# ospi_v12.net
KiCad netlist of a schematic drawn in EAGLE
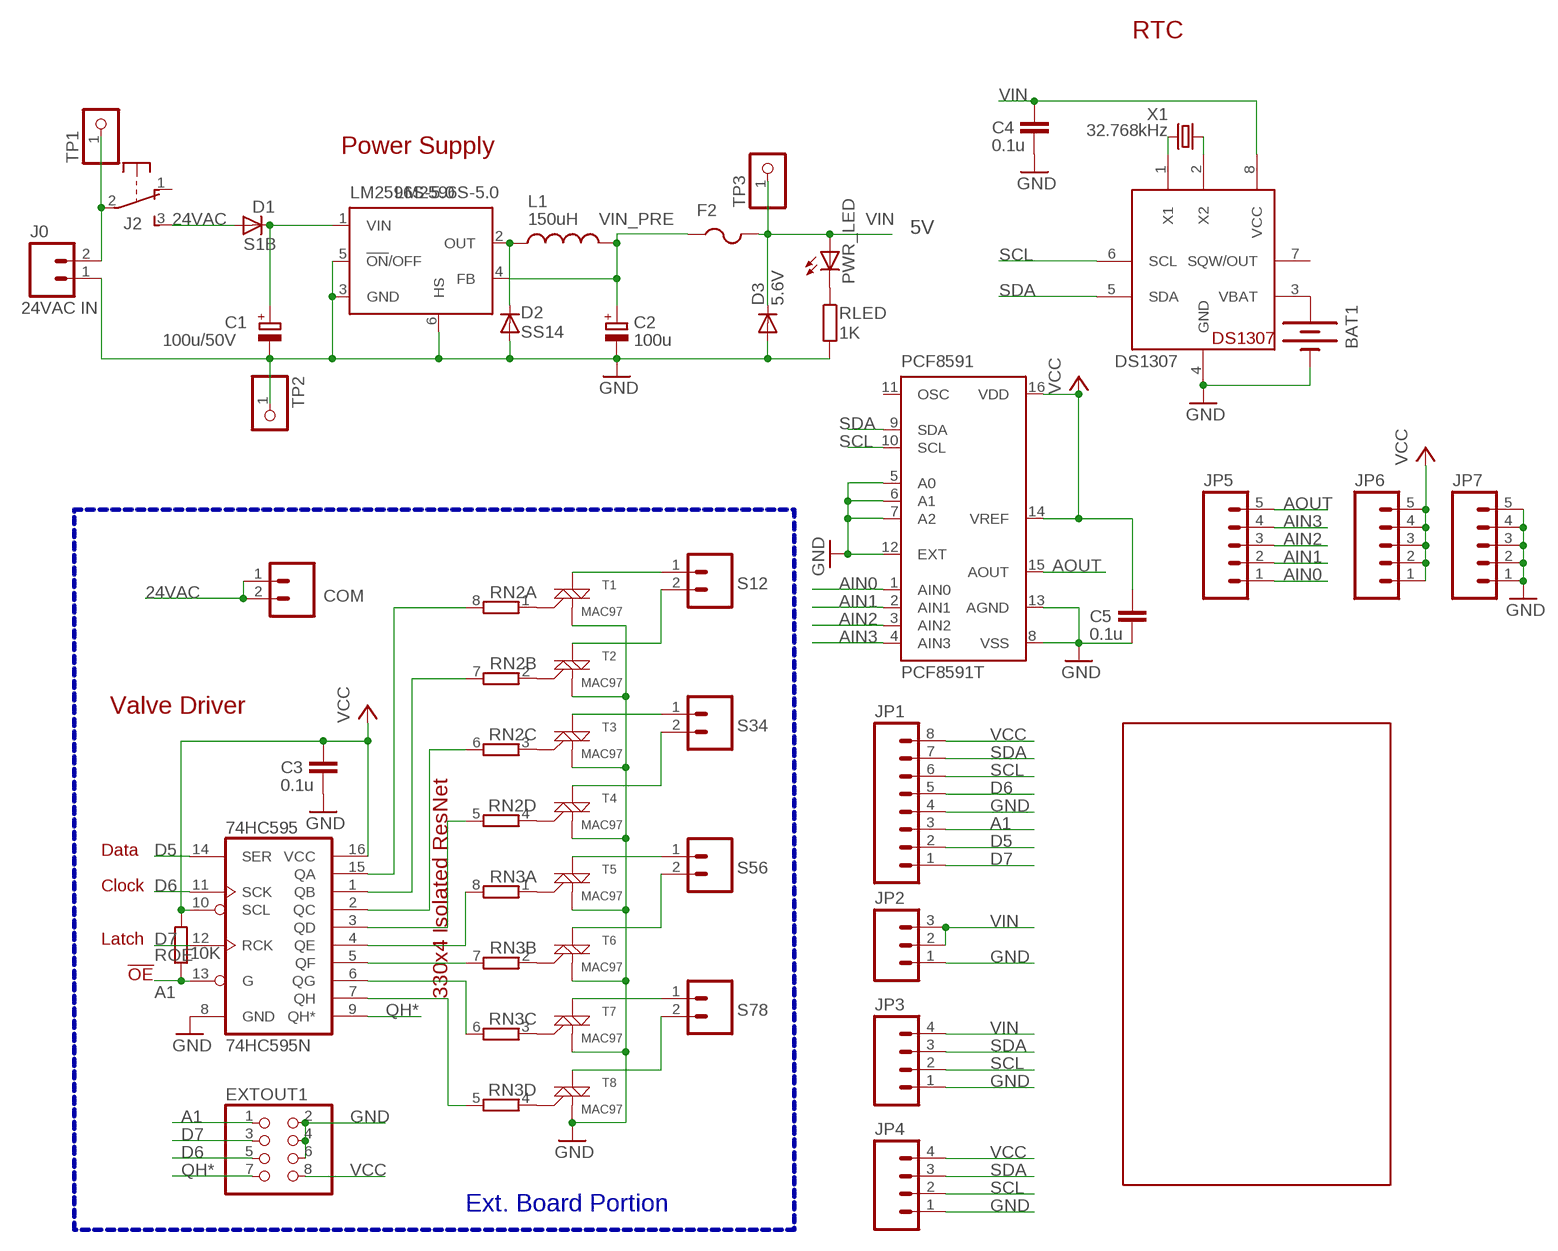
[diagram p0: schematic, sheet 1]

(export (version "E")
  (design (tool "Eeschema 10.0.6"))
  (components
    (comp (ref "74HC595")
      (value "74HC595N")
      (footprint "eagle-import:SO16")
      (libsource (lib "eagle-import") (part "74595DLS"))
    )
    (comp (ref "BAT1")
      (value "BATTERYBATTERY_12MM_SMT")
      (footprint "eagle-import:BATTCON_12MM_SMT")
      (libsource (lib "eagle-import") (part "BATTERYBATTERY_12MM_SMT"))
    )
    (comp (ref "C1")
      (value "100u/50V")
      (footprint "eagle-import:PANASONIC_E")
      (libsource (lib "eagle-import") (part "CPOL-EUE"))
    )
    (comp (ref "C2")
      (value "100u")
      (footprint "eagle-import:PANASONIC_E")
      (libsource (lib "eagle-import") (part "CPOL-EUE"))
    )
    (comp (ref "C3")
      (value "0.1u")
      (footprint "eagle-import:C0805")
      (libsource (lib "eagle-import") (part "C-EUC0805"))
    )
    (comp (ref "C4")
      (value "0.1u")
      (footprint "eagle-import:C0805")
      (libsource (lib "eagle-import") (part "C-EUC0805"))
    )
    (comp (ref "C5")
      (value "0.1u")
      (footprint "eagle-import:C0805")
      (libsource (lib "eagle-import") (part "C-EUC0805"))
    )
    (comp (ref "COM")
      (value "M025MM")
      (footprint "eagle-import:SCREWTERMINAL-5MM-2")
      (libsource (lib "eagle-import") (part "M025MM"))
    )
    (comp (ref "D1")
      (value "S1B")
      (footprint "eagle-import:DO-214AC")
      (libsource (lib "eagle-import") (part "DIODE-DO-214AC"))
    )
    (comp (ref "D2")
      (value "SS14")
      (footprint "eagle-import:DO-214AC")
      (libsource (lib "eagle-import") (part "DIODE-DO-214AC"))
    )
    (comp (ref "D3")
      (value "5.6V")
      (footprint "eagle-import:MINIMELF")
      (libsource (lib "eagle-import") (part "DIODE-MINIMELF"))
    )
    (comp (ref "DS1307")
      (value "DS1307")
      (footprint "eagle-import:SO08")
      (libsource (lib "eagle-import") (part "DS1307SOIC"))
    )
    (comp (ref "EXTOUT1")
      (value "PINHD-2X4/90")
      (footprint "eagle-import:2X04_90")
      (libsource (lib "eagle-import") (part "PINHD-2X4/90"))
    )
    (comp (ref "F2")
      (value "PTCFUSE-1812")
      (footprint "eagle-import:1812")
      (libsource (lib "eagle-import") (part "PTCFUSE-1812"))
    )
    (comp (ref "J0")
      (value "24VAC IN")
      (footprint "eagle-import:SCREWTERMINAL-5MM-2")
      (libsource (lib "eagle-import") (part "M025MM"))
    )
    (comp (ref "J2")
      (value "EG1206")
      (footprint "eagle-import:EG1206")
      (libsource (lib "eagle-import") (part "EG1206"))
    )
    (comp (ref "JP1")
      (value "M08LOCK")
      (footprint "eagle-import:1X08_LOCK")
      (libsource (lib "eagle-import") (part "M08LOCK"))
    )
    (comp (ref "JP2")
      (value "M03LOCK")
      (footprint "eagle-import:1X03_LOCK")
      (libsource (lib "eagle-import") (part "M03LOCK"))
    )
    (comp (ref "JP3")
      (value "M04LOCK")
      (footprint "eagle-import:1X04_LOCK")
      (libsource (lib "eagle-import") (part "M04LOCK"))
    )
    (comp (ref "JP4")
      (value "M04LOCK")
      (footprint "eagle-import:1X04_LOCK")
      (libsource (lib "eagle-import") (part "M04LOCK"))
    )
    (comp (ref "JP5")
      (value "M05LOCK")
      (footprint "eagle-import:1X05_LOCK")
      (libsource (lib "eagle-import") (part "M05LOCK"))
    )
    (comp (ref "JP6")
      (value "M05LOCK")
      (footprint "eagle-import:1X05_LOCK")
      (libsource (lib "eagle-import") (part "M05LOCK"))
    )
    (comp (ref "JP7")
      (value "M05LOCK")
      (footprint "eagle-import:1X05_LOCK")
      (libsource (lib "eagle-import") (part "M05LOCK"))
    )
    (comp (ref "L1")
      (value "150uH")
      (footprint "eagle-import:CDRH125")
      (libsource (lib "eagle-import") (part "INDUCTORPWR"))
    )
    (comp (ref "LM2596S-5.0")
      (value "LM2596S-5.0")
      (footprint "eagle-import:TO263-5")
      (fields (field (name "MF") "NATIONAL SEMICONDUCTOR") (field (name "MPN") "LM2596S-ADJ/NOPB"))
      (libsource (lib "eagle-import") (part "LM2596S"))
    )
    (comp (ref "PCF8591")
      (value "PCF8591T")
      (footprint "eagle-import:SO16W")
      (fields (field (name "MPN") "PCF8591T/2,512"))
      (libsource (lib "eagle-import") (part "PCF8591T"))
    )
    (comp (ref "PWR_LED")
      (value "LEDCHIPLED_0805")
      (footprint "eagle-import:CHIPLED_0805")
      (libsource (lib "eagle-import") (part "LEDCHIPLED_0805"))
    )
    (comp (ref "RLED")
      (value "1K")
      (footprint "eagle-import:R0805")
      (libsource (lib "eagle-import") (part "R-EU_R0805"))
    )
    (comp (ref "RN2")
      (value "4R-NEXB38V")
      (footprint "eagle-import:EXB38V")
      (libsource (lib "eagle-import") (part "4R-NEXB38V"))
    )
    (comp (ref "RN3")
      (value "4R-NEXB38V")
      (footprint "eagle-import:EXB38V")
      (libsource (lib "eagle-import") (part "4R-NEXB38V"))
    )
    (comp (ref "ROE")
      (value "10K")
      (footprint "eagle-import:R0805")
      (libsource (lib "eagle-import") (part "R-EU_R0805"))
    )
    (comp (ref "S12")
      (value "M025MM")
      (footprint "eagle-import:SCREWTERMINAL-5MM-2")
      (libsource (lib "eagle-import") (part "M025MM"))
    )
    (comp (ref "S34")
      (value "M025MM")
      (footprint "eagle-import:SCREWTERMINAL-5MM-2")
      (libsource (lib "eagle-import") (part "M025MM"))
    )
    (comp (ref "S56")
      (value "M025MM")
      (footprint "eagle-import:SCREWTERMINAL-5MM-2")
      (libsource (lib "eagle-import") (part "M025MM"))
    )
    (comp (ref "S78")
      (value "M025MM")
      (footprint "eagle-import:SCREWTERMINAL-5MM-2")
      (libsource (lib "eagle-import") (part "M025MM"))
    )
    (comp (ref "T1")
      (value "MAC97")
      (footprint "eagle-import:SOT223")
      (libsource (lib "eagle-import") (part "MAC97SOT223"))
    )
    (comp (ref "T2")
      (value "MAC97")
      (footprint "eagle-import:SOT223")
      (libsource (lib "eagle-import") (part "MAC97SOT223"))
    )
    (comp (ref "T3")
      (value "MAC97")
      (footprint "eagle-import:SOT223")
      (libsource (lib "eagle-import") (part "MAC97SOT223"))
    )
    (comp (ref "T4")
      (value "MAC97")
      (footprint "eagle-import:SOT223")
      (libsource (lib "eagle-import") (part "MAC97SOT223"))
    )
    (comp (ref "T5")
      (value "MAC97")
      (footprint "eagle-import:SOT223")
      (libsource (lib "eagle-import") (part "MAC97SOT223"))
    )
    (comp (ref "T6")
      (value "MAC97")
      (footprint "eagle-import:SOT223")
      (libsource (lib "eagle-import") (part "MAC97SOT223"))
    )
    (comp (ref "T7")
      (value "MAC97")
      (footprint "eagle-import:SOT223")
      (libsource (lib "eagle-import") (part "MAC97SOT223"))
    )
    (comp (ref "T8")
      (value "MAC97")
      (footprint "eagle-import:SOT223")
      (libsource (lib "eagle-import") (part "MAC97SOT223"))
    )
    (comp (ref "TP1")
      (value "PINHD-1X1CB")
      (footprint "eagle-import:1X01-CLEANBIG")
      (libsource (lib "eagle-import") (part "PINHD-1X1CB"))
    )
    (comp (ref "TP2")
      (value "PINHD-1X1CB")
      (footprint "eagle-import:1X01-CLEANBIG")
      (libsource (lib "eagle-import") (part "PINHD-1X1CB"))
    )
    (comp (ref "TP3")
      (value "PINHD-1X1CB")
      (footprint "eagle-import:1X01-CLEANBIG")
      (libsource (lib "eagle-import") (part "PINHD-1X1CB"))
    )
    (comp (ref "U$2")
      (value "OSPI")
      (footprint "eagle-import:OSPI")
      (libsource (lib "eagle-import") (part "OSPI"))
    )
    (comp (ref "X1")
      (value "32.768kHz")
      (footprint "eagle-import:MM20SS")
      (libsource (lib "eagle-import") (part "CRYSTALMM20SS"))
    )
  )
  (nets
    (net (code "1") (name "/24VAC") (class "Default")
      (node (ref "COM") (pin "1") (pinfunction "1_1") (pintype "passive"))
      (node (ref "COM") (pin "2") (pinfunction "2_2") (pintype "passive"))
      (node (ref "D1") (pin "A") (pinfunction "A_A") (pintype "passive"))
      (node (ref "J2") (pin "3") (pinfunction "S_3") (pintype "passive"))
    )
    (net (code "2") (name "/A1") (class "Default")
      (node (ref "74HC595") (pin "13") (pinfunction "G_13") (pintype "input"))
      (node (ref "EXTOUT1") (pin "1") (pinfunction "1_1") (pintype "passive"))
      (node (ref "JP1") (pin "3") (pinfunction "3_3") (pintype "passive"))
      (node (ref "ROE") (pin "1") (pinfunction "1_1") (pintype "passive"))
    )
    (net (code "3") (name "/AIN0") (class "Default")
      (node (ref "JP5") (pin "1") (pinfunction "1_1") (pintype "passive"))
      (node (ref "PCF8591") (pin "1") (pinfunction "AIN0_1") (pintype "input"))
    )
    (net (code "4") (name "/AIN1") (class "Default")
      (node (ref "JP5") (pin "2") (pinfunction "2_2") (pintype "passive"))
      (node (ref "PCF8591") (pin "2") (pinfunction "AIN1_2") (pintype "input"))
    )
    (net (code "5") (name "/AIN2") (class "Default")
      (node (ref "JP5") (pin "3") (pinfunction "3_3") (pintype "passive"))
      (node (ref "PCF8591") (pin "3") (pinfunction "AIN2_3") (pintype "input"))
    )
    (net (code "6") (name "/AIN3") (class "Default")
      (node (ref "JP5") (pin "4") (pinfunction "4_4") (pintype "passive"))
      (node (ref "PCF8591") (pin "4") (pinfunction "AIN3_4") (pintype "input"))
    )
    (net (code "7") (name "/AOUT") (class "Default")
      (node (ref "JP5") (pin "5") (pinfunction "5_5") (pintype "passive"))
      (node (ref "PCF8591") (pin "15") (pinfunction "AOUT_15") (pintype "output"))
    )
    (net (code "8") (name "/D5") (class "Default")
      (node (ref "74HC595") (pin "14") (pinfunction "SER_14") (pintype "input"))
      (node (ref "JP1") (pin "2") (pinfunction "2_2") (pintype "passive"))
    )
    (net (code "9") (name "/D6") (class "Default")
      (node (ref "74HC595") (pin "11") (pinfunction "SCK_11") (pintype "input"))
      (node (ref "EXTOUT1") (pin "5") (pinfunction "5_5") (pintype "passive"))
      (node (ref "JP1") (pin "5") (pinfunction "5_5") (pintype "passive"))
    )
    (net (code "10") (name "/D7") (class "Default")
      (node (ref "74HC595") (pin "12") (pinfunction "RCK_12") (pintype "input"))
      (node (ref "EXTOUT1") (pin "3") (pinfunction "3_3") (pintype "passive"))
      (node (ref "JP1") (pin "1") (pinfunction "1_1") (pintype "passive"))
    )
    (net (code "11") (name "/QH*") (class "Default")
      (node (ref "74HC595") (pin "9") (pinfunction "QH*_9") (pintype "tri_state"))
      (node (ref "EXTOUT1") (pin "7") (pinfunction "7_7") (pintype "passive"))
    )
    (net (code "12") (name "/SCL") (class "Default")
      (node (ref "DS1307") (pin "6") (pinfunction "SCL_6") (pintype "bidirectional"))
      (node (ref "JP1") (pin "6") (pinfunction "6_6") (pintype "passive"))
      (node (ref "JP3") (pin "2") (pinfunction "2_2") (pintype "passive"))
      (node (ref "JP4") (pin "2") (pinfunction "2_2") (pintype "passive"))
      (node (ref "PCF8591") (pin "10") (pinfunction "SCL_10") (pintype "input"))
    )
    (net (code "13") (name "/SDA") (class "Default")
      (node (ref "DS1307") (pin "5") (pinfunction "SDA_5") (pintype "bidirectional"))
      (node (ref "JP1") (pin "7") (pinfunction "7_7") (pintype "passive"))
      (node (ref "JP3") (pin "3") (pinfunction "3_3") (pintype "passive"))
      (node (ref "JP4") (pin "3") (pinfunction "3_3") (pintype "passive"))
      (node (ref "PCF8591") (pin "9") (pinfunction "SDA_9") (pintype "bidirectional"))
    )
    (net (code "14") (name "/VIN") (class "Default")
      (node (ref "C4") (pin "1") (pinfunction "1_1") (pintype "passive"))
      (node (ref "D3") (pin "C") (pinfunction "C_C") (pintype "passive"))
      (node (ref "DS1307") (pin "8") (pinfunction "VCC_8") (pintype "power_in"))
      (node (ref "F2") (pin "2") (pinfunction "2_2") (pintype "passive"))
      (node (ref "JP2") (pin "2") (pinfunction "2_2") (pintype "passive"))
      (node (ref "JP2") (pin "3") (pinfunction "3_3") (pintype "passive"))
      (node (ref "JP3") (pin "4") (pinfunction "4_4") (pintype "passive"))
      (node (ref "PWR_LED") (pin "A") (pinfunction "A_A") (pintype "passive"))
      (node (ref "TP3") (pin "1") (pinfunction "1_1") (pintype "passive"))
    )
    (net (code "15") (name "/VIN_PRE") (class "Default")
      (node (ref "C2") (pin "+") (pinfunction "+_+") (pintype "passive"))
      (node (ref "F2") (pin "1") (pinfunction "1_1") (pintype "passive"))
      (node (ref "L1") (pin "2") (pinfunction "2_2") (pintype "passive"))
      (node (ref "LM2596S-5.0") (pin "4") (pinfunction "FB_4") (pintype "input"))
    )
    (net (code "16") (name "GND") (class "Default")
      (node (ref "74HC595") (pin "8") (pinfunction "GND_8") (pintype "power_in"))
      (node (ref "BAT1") (pin "P$1") (pinfunction "-_P$1") (pintype "power_in"))
      (node (ref "C1") (pin "-") (pinfunction "-_-") (pintype "passive"))
      (node (ref "C2") (pin "-") (pinfunction "-_-") (pintype "passive"))
      (node (ref "C3") (pin "2") (pinfunction "2_2") (pintype "passive"))
      (node (ref "C4") (pin "2") (pinfunction "2_2") (pintype "passive"))
      (node (ref "C5") (pin "2") (pinfunction "2_2") (pintype "passive"))
      (node (ref "D2") (pin "A") (pinfunction "A_A") (pintype "passive"))
      (node (ref "D3") (pin "A") (pinfunction "A_A") (pintype "passive"))
      (node (ref "DS1307") (pin "4") (pinfunction "GND_4") (pintype "power_in"))
      (node (ref "EXTOUT1") (pin "2") (pinfunction "2_2") (pintype "passive"))
      (node (ref "EXTOUT1") (pin "4") (pinfunction "4_4") (pintype "passive"))
      (node (ref "EXTOUT1") (pin "6") (pinfunction "6_6") (pintype "passive"))
      (node (ref "J0") (pin "1") (pinfunction "1_1") (pintype "passive"))
      (node (ref "JP1") (pin "4") (pinfunction "4_4") (pintype "passive"))
      (node (ref "JP2") (pin "1") (pinfunction "1_1") (pintype "passive"))
      (node (ref "JP3") (pin "1") (pinfunction "1_1") (pintype "passive"))
      (node (ref "JP4") (pin "1") (pinfunction "1_1") (pintype "passive"))
      (node (ref "JP7") (pin "1") (pinfunction "1_1") (pintype "passive"))
      (node (ref "JP7") (pin "2") (pinfunction "2_2") (pintype "passive"))
      (node (ref "JP7") (pin "3") (pinfunction "3_3") (pintype "passive"))
      (node (ref "JP7") (pin "4") (pinfunction "4_4") (pintype "passive"))
      (node (ref "JP7") (pin "5") (pinfunction "5_5") (pintype "passive"))
      (node (ref "LM2596S-5.0") (pin "3") (pinfunction "GND_3") (pintype "power_in"))
      (node (ref "LM2596S-5.0") (pin "5") (pinfunction "~{ON}/OFF_5") (pintype "input"))
      (node (ref "LM2596S-5.0") (pin "6") (pinfunction "HS_6") (pintype "power_in"))
      (node (ref "PCF8591") (pin "12") (pinfunction "EXT_12") (pintype "input"))
      (node (ref "PCF8591") (pin "13") (pinfunction "AGND_13") (pintype "power_in"))
      (node (ref "PCF8591") (pin "5") (pinfunction "A0_5") (pintype "input"))
      (node (ref "PCF8591") (pin "6") (pinfunction "A1_6") (pintype "input"))
      (node (ref "PCF8591") (pin "7") (pinfunction "A2_7") (pintype "input"))
      (node (ref "PCF8591") (pin "8") (pinfunction "VSS_8") (pintype "power_in"))
      (node (ref "RLED") (pin "2") (pinfunction "2_2") (pintype "passive"))
      (node (ref "T1") (pin "1") (pinfunction "M1_1") (pintype "bidirectional"))
      (node (ref "T2") (pin "1") (pinfunction "M1_1") (pintype "bidirectional"))
      (node (ref "T3") (pin "1") (pinfunction "M1_1") (pintype "bidirectional"))
      (node (ref "T4") (pin "1") (pinfunction "M1_1") (pintype "bidirectional"))
      (node (ref "T5") (pin "1") (pinfunction "M1_1") (pintype "bidirectional"))
      (node (ref "T6") (pin "1") (pinfunction "M1_1") (pintype "bidirectional"))
      (node (ref "T7") (pin "1") (pinfunction "M1_1") (pintype "bidirectional"))
      (node (ref "T8") (pin "1") (pinfunction "M1_1") (pintype "bidirectional"))
      (node (ref "TP2") (pin "1") (pinfunction "1_1") (pintype "passive"))
    )
    (net (code "17") (name "Net-(74HC595-QA)") (class "Default")
      (node (ref "74HC595") (pin "15") (pinfunction "QA_15") (pintype "tri_state"))
      (node (ref "RN2") (pin "8") (pinfunction "2_8") (pintype "passive"))
    )
    (net (code "18") (name "Net-(74HC595-QB)") (class "Default")
      (node (ref "74HC595") (pin "1") (pinfunction "QB_1") (pintype "tri_state"))
      (node (ref "RN2") (pin "7") (pinfunction "2_7") (pintype "passive"))
    )
    (net (code "19") (name "Net-(74HC595-QC)") (class "Default")
      (node (ref "74HC595") (pin "2") (pinfunction "QC_2") (pintype "tri_state"))
      (node (ref "RN2") (pin "6") (pinfunction "2_6") (pintype "passive"))
    )
    (net (code "20") (name "Net-(74HC595-QD)") (class "Default")
      (node (ref "74HC595") (pin "3") (pinfunction "QD_3") (pintype "tri_state"))
      (node (ref "RN2") (pin "5") (pinfunction "2_5") (pintype "passive"))
    )
    (net (code "21") (name "Net-(74HC595-QE)") (class "Default")
      (node (ref "74HC595") (pin "4") (pinfunction "QE_4") (pintype "tri_state"))
      (node (ref "RN3") (pin "8") (pinfunction "2_8") (pintype "passive"))
    )
    (net (code "22") (name "Net-(74HC595-QF)") (class "Default")
      (node (ref "74HC595") (pin "5") (pinfunction "QF_5") (pintype "tri_state"))
      (node (ref "RN3") (pin "7") (pinfunction "2_7") (pintype "passive"))
    )
    (net (code "23") (name "Net-(74HC595-QG)") (class "Default")
      (node (ref "74HC595") (pin "6") (pinfunction "QG_6") (pintype "tri_state"))
      (node (ref "RN3") (pin "6") (pinfunction "2_6") (pintype "passive"))
    )
    (net (code "24") (name "Net-(74HC595-QH)") (class "Default")
      (node (ref "74HC595") (pin "7") (pinfunction "QH_7") (pintype "tri_state"))
      (node (ref "RN3") (pin "5") (pinfunction "2_5") (pintype "passive"))
    )
    (net (code "25") (name "Net-(BAT1-+)") (class "Default")
      (node (ref "BAT1") (pin "P$2") (pinfunction "+_P$2") (pintype "power_in"))
      (node (ref "DS1307") (pin "3") (pinfunction "VBAT_3") (pintype "power_in"))
    )
    (net (code "26") (name "Net-(DS1307-X1)") (class "Default")
      (node (ref "DS1307") (pin "1") (pinfunction "X1_1") (pintype "passive"))
      (node (ref "X1") (pin "1") (pinfunction "1_1") (pintype "passive"))
    )
    (net (code "27") (name "Net-(DS1307-X2)") (class "Default")
      (node (ref "DS1307") (pin "2") (pinfunction "X2_2") (pintype "passive"))
      (node (ref "X1") (pin "4") (pinfunction "2_4") (pintype "passive"))
    )
    (net (code "28") (name "Net-(J2-P)") (class "Default")
      (node (ref "J0") (pin "2") (pinfunction "2_2") (pintype "passive"))
      (node (ref "J2") (pin "2") (pinfunction "P_2") (pintype "passive"))
      (node (ref "TP1") (pin "1") (pinfunction "1_1") (pintype "passive"))
    )
    (net (code "29") (name "Net-(LM2596S-5.0-OUT)") (class "Default")
      (node (ref "D2") (pin "C") (pinfunction "C_C") (pintype "passive"))
      (node (ref "L1") (pin "1") (pinfunction "1_1") (pintype "passive"))
      (node (ref "LM2596S-5.0") (pin "2") (pinfunction "OUT_2") (pintype "output"))
    )
    (net (code "30") (name "Net-(LM2596S-5.0-VIN)") (class "Default")
      (node (ref "C1") (pin "+") (pinfunction "+_+") (pintype "passive"))
      (node (ref "D1") (pin "C") (pinfunction "C_C") (pintype "passive"))
      (node (ref "LM2596S-5.0") (pin "1") (pinfunction "VIN_1") (pintype "input"))
    )
    (net (code "31") (name "Net-(PWR_LED-PadC)") (class "Default")
      (node (ref "PWR_LED") (pin "C") (pinfunction "C_C") (pintype "passive"))
      (node (ref "RLED") (pin "1") (pinfunction "1_1") (pintype "passive"))
    )
    (net (code "32") (name "Net-(RN2B-1)") (class "Default")
      (node (ref "RN2") (pin "2") (pinfunction "1_2") (pintype "passive"))
      (node (ref "T2") (pin "3") (pinfunction "G_3") (pintype "bidirectional"))
    )
    (net (code "33") (name "Net-(RN2C-1)") (class "Default")
      (node (ref "RN2") (pin "3") (pinfunction "1_3") (pintype "passive"))
      (node (ref "T3") (pin "3") (pinfunction "G_3") (pintype "bidirectional"))
    )
    (net (code "34") (name "Net-(RN2D-1)") (class "Default")
      (node (ref "RN2") (pin "4") (pinfunction "1_4") (pintype "passive"))
      (node (ref "T4") (pin "3") (pinfunction "G_3") (pintype "bidirectional"))
    )
    (net (code "35") (name "Net-(RN3B-1)") (class "Default")
      (node (ref "RN3") (pin "2") (pinfunction "1_2") (pintype "passive"))
      (node (ref "T6") (pin "3") (pinfunction "G_3") (pintype "bidirectional"))
    )
    (net (code "36") (name "Net-(RN3C-1)") (class "Default")
      (node (ref "RN3") (pin "3") (pinfunction "1_3") (pintype "passive"))
      (node (ref "T7") (pin "3") (pinfunction "G_3") (pintype "bidirectional"))
    )
    (net (code "37") (name "Net-(RN3D-1)") (class "Default")
      (node (ref "RN3") (pin "4") (pinfunction "1_4") (pintype "passive"))
      (node (ref "T8") (pin "3") (pinfunction "G_3") (pintype "bidirectional"))
    )
    (net (code "38") (name "Net-(T1-G)") (class "Default")
      (node (ref "RN2") (pin "1") (pinfunction "1_1") (pintype "passive"))
      (node (ref "T1") (pin "3") (pinfunction "G_3") (pintype "bidirectional"))
    )
    (net (code "39") (name "Net-(T1-M2)") (class "Default")
      (node (ref "S12") (pin "1") (pinfunction "1_1") (pintype "passive"))
      (node (ref "T1") (pin "4") (pinfunction "M2_4") (pintype "bidirectional"))
    )
    (net (code "40") (name "Net-(T2-M2)") (class "Default")
      (node (ref "S12") (pin "2") (pinfunction "2_2") (pintype "passive"))
      (node (ref "T2") (pin "4") (pinfunction "M2_4") (pintype "bidirectional"))
    )
    (net (code "41") (name "Net-(T3-M2)") (class "Default")
      (node (ref "S34") (pin "1") (pinfunction "1_1") (pintype "passive"))
      (node (ref "T3") (pin "4") (pinfunction "M2_4") (pintype "bidirectional"))
    )
    (net (code "42") (name "Net-(T4-M2)") (class "Default")
      (node (ref "S34") (pin "2") (pinfunction "2_2") (pintype "passive"))
      (node (ref "T4") (pin "4") (pinfunction "M2_4") (pintype "bidirectional"))
    )
    (net (code "43") (name "Net-(T5-G)") (class "Default")
      (node (ref "RN3") (pin "1") (pinfunction "1_1") (pintype "passive"))
      (node (ref "T5") (pin "3") (pinfunction "G_3") (pintype "bidirectional"))
    )
    (net (code "44") (name "Net-(T5-M2)") (class "Default")
      (node (ref "S56") (pin "1") (pinfunction "1_1") (pintype "passive"))
      (node (ref "T5") (pin "4") (pinfunction "M2_4") (pintype "bidirectional"))
    )
    (net (code "45") (name "Net-(T6-M2)") (class "Default")
      (node (ref "S56") (pin "2") (pinfunction "2_2") (pintype "passive"))
      (node (ref "T6") (pin "4") (pinfunction "M2_4") (pintype "bidirectional"))
    )
    (net (code "46") (name "Net-(T7-M2)") (class "Default")
      (node (ref "S78") (pin "1") (pinfunction "1_1") (pintype "passive"))
      (node (ref "T7") (pin "4") (pinfunction "M2_4") (pintype "bidirectional"))
    )
    (net (code "47") (name "Net-(T8-M2)") (class "Default")
      (node (ref "S78") (pin "2") (pinfunction "2_2") (pintype "passive"))
      (node (ref "T8") (pin "4") (pinfunction "M2_4") (pintype "bidirectional"))
    )
    (net (code "48") (name "VCC") (class "Default")
      (node (ref "74HC595") (pin "10") (pinfunction "SCL_10") (pintype "input"))
      (node (ref "74HC595") (pin "16") (pinfunction "VCC_16") (pintype "power_in"))
      (node (ref "C3") (pin "1") (pinfunction "1_1") (pintype "passive"))
      (node (ref "C5") (pin "1") (pinfunction "1_1") (pintype "passive"))
      (node (ref "EXTOUT1") (pin "8") (pinfunction "8_8") (pintype "passive"))
      (node (ref "JP1") (pin "8") (pinfunction "8_8") (pintype "passive"))
      (node (ref "JP4") (pin "4") (pinfunction "4_4") (pintype "passive"))
      (node (ref "JP6") (pin "1") (pinfunction "1_1") (pintype "passive"))
      (node (ref "JP6") (pin "2") (pinfunction "2_2") (pintype "passive"))
      (node (ref "JP6") (pin "3") (pinfunction "3_3") (pintype "passive"))
      (node (ref "JP6") (pin "4") (pinfunction "4_4") (pintype "passive"))
      (node (ref "JP6") (pin "5") (pinfunction "5_5") (pintype "passive"))
      (node (ref "PCF8591") (pin "14") (pinfunction "VREF_14") (pintype "input"))
      (node (ref "PCF8591") (pin "16") (pinfunction "VDD_16") (pintype "power_in"))
      (node (ref "ROE") (pin "2") (pinfunction "2_2") (pintype "passive"))
    )
    (net (code "49") (name "unconnected-(DS1307-SQW{slash}OUT-Pad7)") (class "Default")
      (node (ref "DS1307") (pin "7") (pinfunction "SQW/OUT_7") (pintype "bidirectional"))
    )
    (net (code "50") (name "unconnected-(J2-O-Pad1)") (class "Default")
      (node (ref "J2") (pin "1") (pinfunction "O_1") (pintype "passive"))
    )
    (net (code "51") (name "unconnected-(PCF8591-OSC-Pad11)") (class "Default")
      (node (ref "PCF8591") (pin "11") (pinfunction "OSC_11") (pintype "input"))
    )
  )
)
